# BME280.net
KiCad netlist of a schematic drawn in Altium Designer
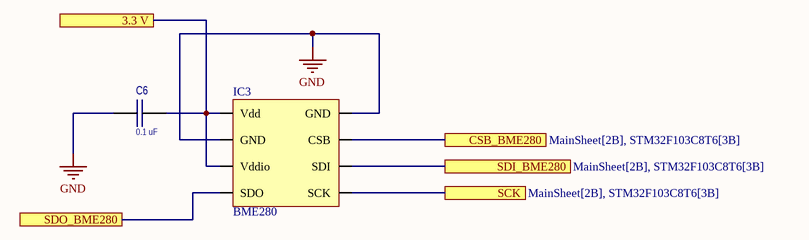
[diagram p0: BME280.SchDoc]

(export (version "E")
  (design (tool "Eeschema 10.0.6"))
  (components
    (comp (ref "C6")
      (value "0.1 uF")
      (footprint "C_0805")
      (description "Capacitor")
      (libsource (lib "capacitors") (part "C0805"))
    )
    (comp (ref "IC3") (value "BME280") (footprint "BME280") (libsource (lib "Sensors") (part "BME280")))
  )
  (nets
    (net (code "1") (name "/3.3 V") (class "Default")
      (node (ref "C6") (pin "1") (pinfunction "1_1") (pintype "passive"))
      (node (ref "IC3") (pin "6") (pinfunction "Vddio_6") (pintype "passive"))
      (node (ref "IC3") (pin "8") (pinfunction "Vdd_8") (pintype "passive"))
    )
    (net (code "2") (name "/CSB_BME280") (class "Default")
      (node (ref "IC3") (pin "2") (pinfunction "CSB_2") (pintype "passive"))
    )
    (net (code "3") (name "/SCK") (class "Default")
      (node (ref "IC3") (pin "4") (pinfunction "SCK_4") (pintype "passive"))
    )
    (net (code "4") (name "/SDI_BME280") (class "Default")
      (node (ref "IC3") (pin "3") (pinfunction "SDI_3") (pintype "passive"))
    )
    (net (code "5") (name "/SDO_BME280") (class "Default")
      (node (ref "IC3") (pin "5") (pinfunction "SDO_5") (pintype "passive"))
    )
    (net (code "6") (name "GND") (class "Default")
      (node (ref "C6") (pin "2") (pinfunction "2_2") (pintype "passive"))
      (node (ref "IC3") (pin "1") (pinfunction "GND_1") (pintype "passive"))
      (node (ref "IC3") (pin "7") (pinfunction "GND_7") (pintype "passive"))
    )
  )
)
